# apex-lumia.net
KiCad netlist of a schematic drawn in EAGLE
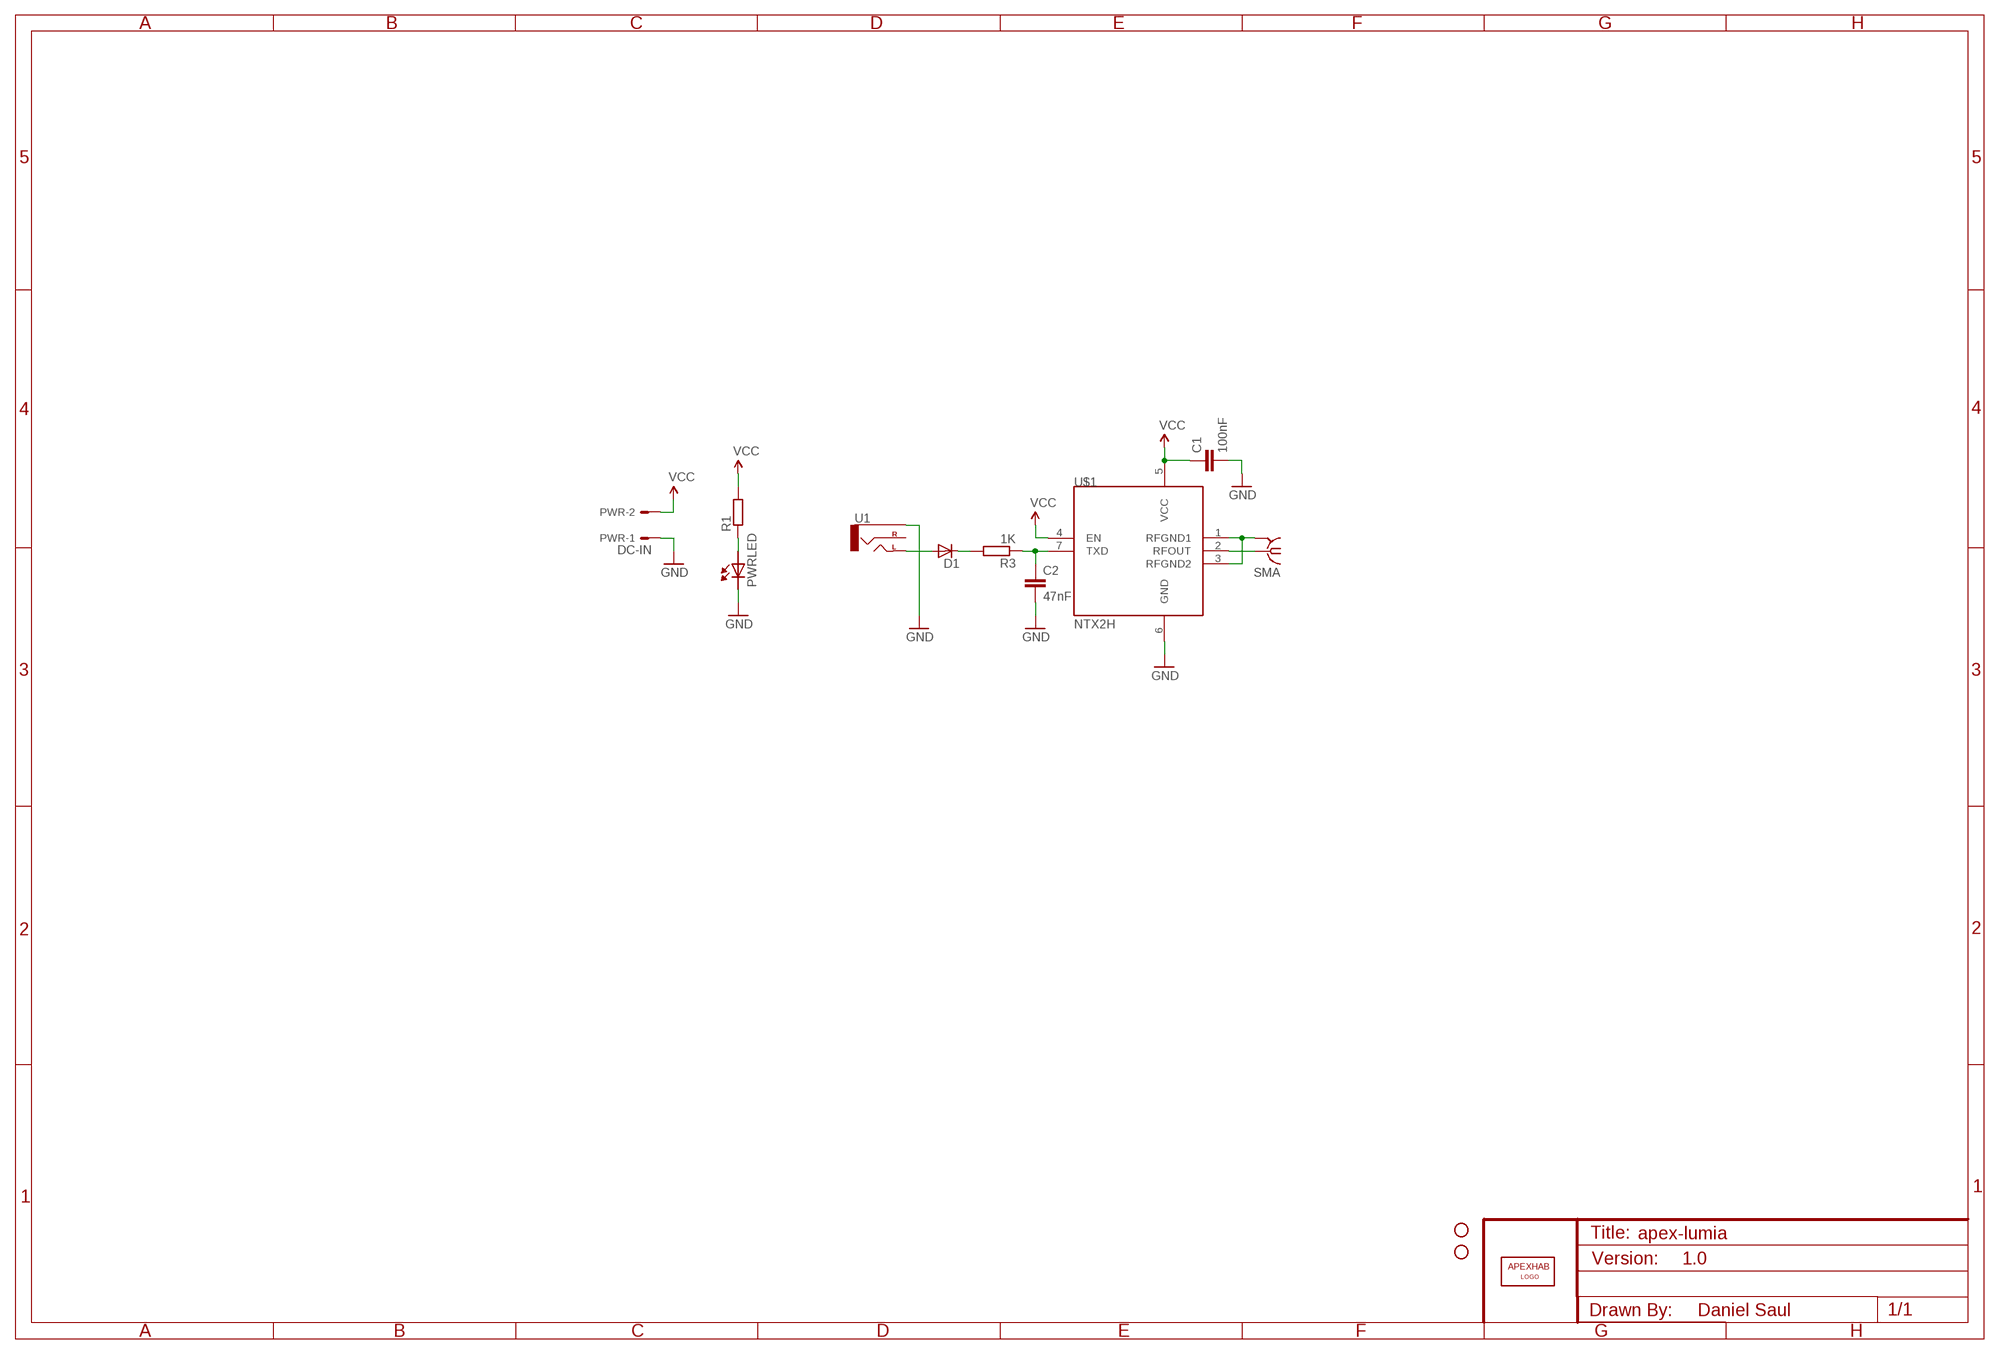
[diagram p0: schematic, sheet 1]

(export (version "E")
  (design (tool "Eeschema 10.0.6"))
  (components
    (comp (ref "C1")
      (value "100nF")
      (footprint "eagle-import:C0805K")
      (libsource (lib "eagle-import") (part "C-EUC0805K"))
    )
    (comp (ref "C2")
      (value "47nF")
      (footprint "eagle-import:C0805K")
      (libsource (lib "eagle-import") (part "C-EUC0805K"))
    )
    (comp (ref "D1")
      (value "CGRM4001-G")
      (footprint "eagle-import:SOD-123_MINI-SMA")
      (libsource (lib "eagle-import") (part "CGRM400-G1"))
    )
    (comp (ref "JP1")
      (value "APEXHAB-LOGO_APEXHAB-SMALL")
      (footprint "eagle-import:APEXHAB-LOGO-SMALL")
      (libsource (lib "eagle-import") (part "APEXHAB-LOGO_APEXHAB-SMALL"))
    )
    (comp (ref "JP2")
      (value "STAND-OFF")
      (footprint "eagle-import:STAND-OFF")
      (libsource (lib "eagle-import") (part "STAND-OFF"))
    )
    (comp (ref "JP3")
      (value "STAND-OFF")
      (footprint "eagle-import:STAND-OFF")
      (libsource (lib "eagle-import") (part "STAND-OFF"))
    )
    (comp (ref "PWR")
      (value "DC-IN")
      (footprint "eagle-import:7395-02")
      (libsource (lib "eagle-import") (part "22-?-0205-7028"))
    )
    (comp (ref "PWRLED")
      (value "LED_0603")
      (footprint "eagle-import:CHIPLED_0603")
      (libsource (lib "eagle-import") (part "LED_0603"))
    )
    (comp (ref "R1")
      (value "R-EU_R0805")
      (footprint "eagle-import:R0805")
      (libsource (lib "eagle-import") (part "R-EU_R0805"))
    )
    (comp (ref "R3")
      (value "1K")
      (footprint "eagle-import:R0805")
      (libsource (lib "eagle-import") (part "R-EU_R0805"))
    )
    (comp (ref "SMA")
      (value "SMA-142-0701-801/806")
      (footprint "eagle-import:J502-ND-142-0701-801_806")
      (fields (field (name "MF") "JOHNSON COMPONENTS") (field (name "MPN") "142-0701-801"))
      (libsource (lib "eagle-import") (part "SMA-142-0701-801/806"))
    )
    (comp (ref "U$1")
      (value "NTX2H")
      (footprint "eagle-import:NTX2H")
      (libsource (lib "eagle-import") (part "NTX2H"))
    )
    (comp (ref "U1")
      (value "AUDIO-JACKPTH")
      (footprint "eagle-import:AUDIO-JACK")
      (libsource (lib "eagle-import") (part "AUDIO-JACKPTH"))
    )
  )
  (nets
    (net (code "1") (name "GND") (class "Default")
      (node (ref "C1") (pin "2") (pinfunction "2_2") (pintype "passive"))
      (node (ref "C2") (pin "2") (pinfunction "2_2") (pintype "passive"))
      (node (ref "PWR") (pin "1") (pinfunction "S_1") (pintype "passive"))
      (node (ref "PWRLED") (pin "C") (pinfunction "C_C") (pintype "passive"))
      (node (ref "U$1") (pin "6") (pinfunction "GND_6") (pintype "passive"))
      (node (ref "U1") (pin "SLEEVE") (pinfunction "SLEEVE_SLEEVE") (pintype "bidirectional"))
    )
    (net (code "2") (name "Net-(D1-PadC)") (class "Default")
      (node (ref "D1") (pin "C") (pinfunction "C_C") (pintype "passive"))
      (node (ref "R3") (pin "2") (pinfunction "2_2") (pintype "passive"))
    )
    (net (code "3") (name "Net-(PWRLED-PadA)") (class "Default")
      (node (ref "PWRLED") (pin "A") (pinfunction "A_A") (pintype "passive"))
      (node (ref "R1") (pin "1") (pinfunction "1_1") (pintype "passive"))
    )
    (net (code "4") (name "Net-(SMAB-GND)") (class "Default")
      (node (ref "SMA") (pin "G@1") (pinfunction "GND_G@1") (pintype "power_in"))
      (node (ref "U$1") (pin "1") (pinfunction "RFGND1_1") (pintype "passive"))
      (node (ref "U$1") (pin "3") (pinfunction "RFGND2_3") (pintype "passive"))
    )
    (net (code "5") (name "Net-(U$1-RFOUT)") (class "Default")
      (node (ref "SMA") (pin "1") (pinfunction "1_1") (pintype "passive"))
      (node (ref "U$1") (pin "2") (pinfunction "RFOUT_2") (pintype "output"))
    )
    (net (code "6") (name "Net-(U$1-TXD)") (class "Default")
      (node (ref "C2") (pin "1") (pinfunction "1_1") (pintype "passive"))
      (node (ref "R3") (pin "1") (pinfunction "1_1") (pintype "passive"))
      (node (ref "U$1") (pin "7") (pinfunction "TXD_7") (pintype "input"))
    )
    (net (code "7") (name "Net-(U1-LEFT)") (class "Default")
      (node (ref "D1") (pin "A") (pinfunction "A_A") (pintype "passive"))
      (node (ref "U1") (pin "TIP") (pinfunction "LEFT_TIP") (pintype "bidirectional"))
    )
    (net (code "8") (name "VCC") (class "Default")
      (node (ref "C1") (pin "1") (pinfunction "1_1") (pintype "passive"))
      (node (ref "PWR") (pin "2") (pinfunction "S_2") (pintype "passive"))
      (node (ref "R1") (pin "2") (pinfunction "2_2") (pintype "passive"))
      (node (ref "U$1") (pin "4") (pinfunction "EN_4") (pintype "input"))
      (node (ref "U$1") (pin "5") (pinfunction "VCC_5") (pintype "passive"))
    )
    (net (code "9") (name "unconnected-(U1-RIGHT-PadRING)") (class "Default")
      (node (ref "U1") (pin "RING") (pinfunction "RIGHT_RING") (pintype "bidirectional"))
    )
  )
)
